# TIA_Schematic_19_Jan_2017.net
KiCad netlist of a schematic drawn in EAGLE
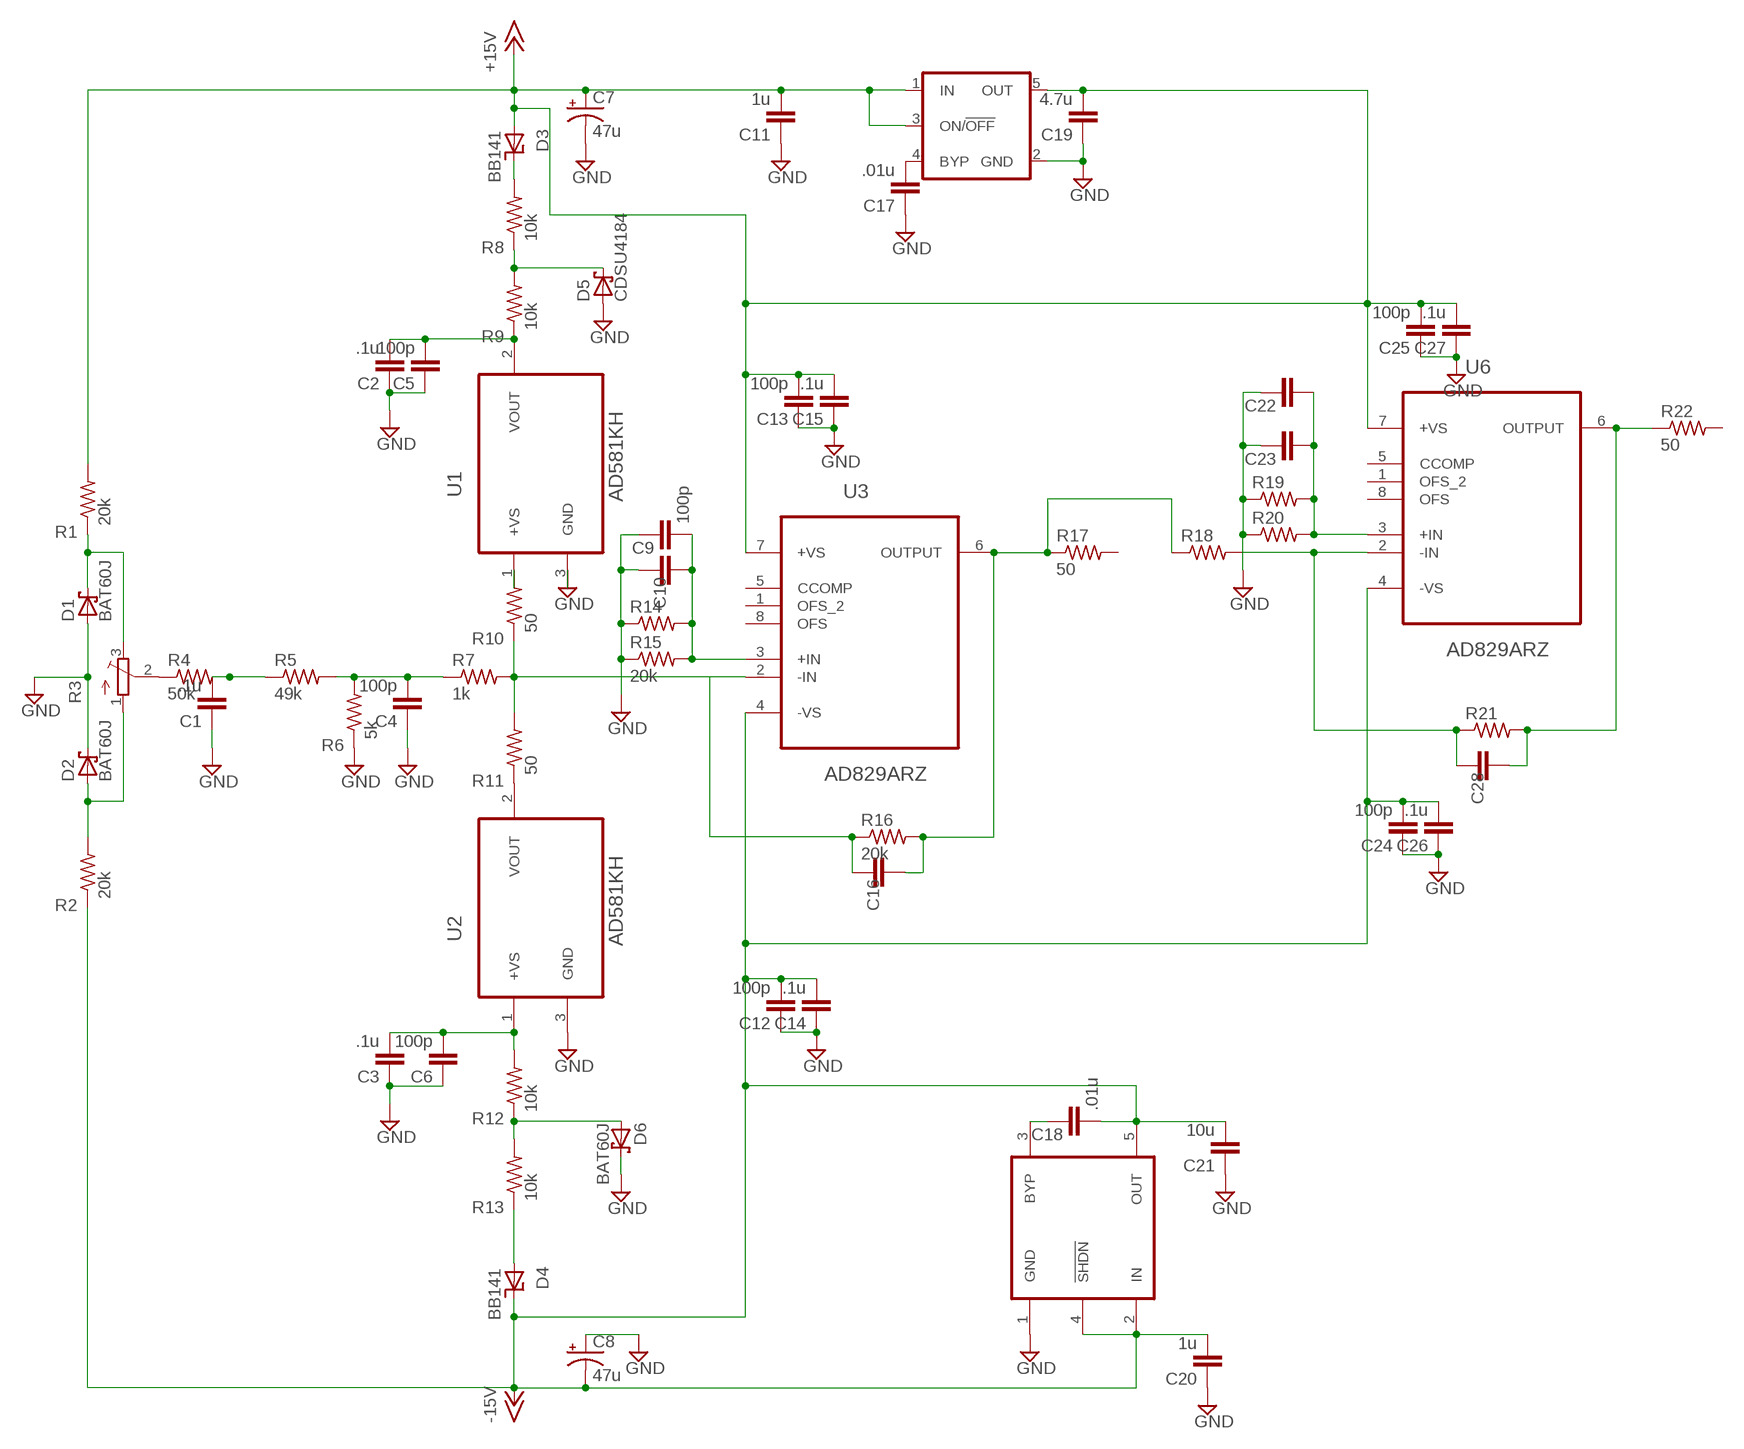
[diagram p0: schematic, sheet 1]

(export (version "E")
  (design (tool "Eeschema 10.0.6"))
  (components
    (comp (ref "C1")
      (value ".1u")
      (footprint "eagle-import:C0603")
      (libsource (lib "eagle-import") (part "C-EUC0603"))
    )
    (comp (ref "C2")
      (value ".1u")
      (footprint "eagle-import:C0603")
      (libsource (lib "eagle-import") (part "C-EUC0603"))
    )
    (comp (ref "C3")
      (value ".1u")
      (footprint "eagle-import:C0603")
      (libsource (lib "eagle-import") (part "C-EUC0603"))
    )
    (comp (ref "C4")
      (value "100p")
      (footprint "eagle-import:C0603")
      (libsource (lib "eagle-import") (part "C-EUC0603"))
    )
    (comp (ref "C5")
      (value "100p")
      (footprint "eagle-import:C0603")
      (libsource (lib "eagle-import") (part "C-EUC0603"))
    )
    (comp (ref "C6")
      (value "100p")
      (footprint "eagle-import:C0603")
      (libsource (lib "eagle-import") (part "C-EUC0603"))
    )
    (comp (ref "C7")
      (value "47u")
      (footprint "eagle-import:ETR3")
      (libsource (lib "eagle-import") (part "CPOL-USETR3"))
    )
    (comp (ref "C8")
      (value "47u")
      (footprint "eagle-import:ETR3")
      (libsource (lib "eagle-import") (part "CPOL-USETR3"))
    )
    (comp (ref "C9")
      (value "100p")
      (footprint "eagle-import:C0603")
      (libsource (lib "eagle-import") (part "C-EUC0603"))
    )
    (comp (ref "C10")
      (value "C-EUC0603")
      (footprint "eagle-import:C0603")
      (libsource (lib "eagle-import") (part "C-EUC0603"))
    )
    (comp (ref "C11")
      (value "1u")
      (footprint "eagle-import:C0603")
      (libsource (lib "eagle-import") (part "C-EUC0603"))
    )
    (comp (ref "C12")
      (value "100p")
      (footprint "eagle-import:C0603")
      (libsource (lib "eagle-import") (part "C-EUC0603"))
    )
    (comp (ref "C13")
      (value "100p")
      (footprint "eagle-import:C0603")
      (libsource (lib "eagle-import") (part "C-EUC0603"))
    )
    (comp (ref "C14")
      (value ".1u")
      (footprint "eagle-import:C0603")
      (libsource (lib "eagle-import") (part "C-EUC0603"))
    )
    (comp (ref "C15")
      (value ".1u")
      (footprint "eagle-import:C0603")
      (libsource (lib "eagle-import") (part "C-EUC0603"))
    )
    (comp (ref "C16")
      (value "C-EUC0603")
      (footprint "eagle-import:C0603")
      (libsource (lib "eagle-import") (part "C-EUC0603"))
    )
    (comp (ref "C17")
      (value ".01u")
      (footprint "eagle-import:C0603")
      (libsource (lib "eagle-import") (part "C-EUC0603"))
    )
    (comp (ref "C18")
      (value ".01u")
      (footprint "eagle-import:C0603")
      (libsource (lib "eagle-import") (part "C-EUC0603"))
    )
    (comp (ref "C19")
      (value "4.7u")
      (footprint "eagle-import:C0603")
      (libsource (lib "eagle-import") (part "C-EUC0603"))
    )
    (comp (ref "C20")
      (value "1u")
      (footprint "eagle-import:C0603")
      (libsource (lib "eagle-import") (part "C-EUC0603"))
    )
    (comp (ref "C21")
      (value "10u")
      (footprint "eagle-import:C0603")
      (libsource (lib "eagle-import") (part "C-EUC0603"))
    )
    (comp (ref "C22")
      (value "C-EUC0603")
      (footprint "eagle-import:C0603")
      (libsource (lib "eagle-import") (part "C-EUC0603"))
    )
    (comp (ref "C23")
      (value "C-EUC0603")
      (footprint "eagle-import:C0603")
      (libsource (lib "eagle-import") (part "C-EUC0603"))
    )
    (comp (ref "C24")
      (value "100p")
      (footprint "eagle-import:C0603")
      (libsource (lib "eagle-import") (part "C-EUC0603"))
    )
    (comp (ref "C25")
      (value "100p")
      (footprint "eagle-import:C0603")
      (libsource (lib "eagle-import") (part "C-EUC0603"))
    )
    (comp (ref "C26")
      (value ".1u")
      (footprint "eagle-import:C0603")
      (libsource (lib "eagle-import") (part "C-EUC0603"))
    )
    (comp (ref "C27")
      (value ".1u")
      (footprint "eagle-import:C0603")
      (libsource (lib "eagle-import") (part "C-EUC0603"))
    )
    (comp (ref "C28")
      (value "C-EUC0603")
      (footprint "eagle-import:C0603")
      (libsource (lib "eagle-import") (part "C-EUC0603"))
    )
    (comp (ref "D1")
      (value "BAT60J")
      (footprint "eagle-import:SOD323_ST")
      (libsource (lib "eagle-import") (part "BAT60J"))
    )
    (comp (ref "D2")
      (value "BAT60J")
      (footprint "eagle-import:SOD323_ST")
      (libsource (lib "eagle-import") (part "BAT60J"))
    )
    (comp (ref "D3")
      (value "BB141")
      (footprint "eagle-import:SOD523")
      (libsource (lib "eagle-import") (part "BB141"))
    )
    (comp (ref "D4")
      (value "BB141")
      (footprint "eagle-import:SOD523")
      (libsource (lib "eagle-import") (part "BB141"))
    )
    (comp (ref "D5")
      (value "CDSU4184")
      (footprint "eagle-import:SOD323_ST")
      (libsource (lib "eagle-import") (part "BAT60J"))
    )
    (comp (ref "D6")
      (value "BAT60J")
      (footprint "eagle-import:SOD323_ST")
      (libsource (lib "eagle-import") (part "BAT60J"))
    )
    (comp (ref "R1")
      (value "20k")
      (footprint "eagle-import:R0603")
      (libsource (lib "eagle-import") (part "R-US_R0603"))
    )
    (comp (ref "R2")
      (value "20k")
      (footprint "eagle-import:R0603")
      (libsource (lib "eagle-import") (part "R-US_R0603"))
    )
    (comp (ref "R3")
      (value "TRIM_EU-3223G")
      (footprint "eagle-import:3223G")
      (libsource (lib "eagle-import") (part "TRIM_EU-3223G"))
    )
    (comp (ref "R4")
      (value "50k")
      (footprint "eagle-import:R0603")
      (libsource (lib "eagle-import") (part "R-US_R0603"))
    )
    (comp (ref "R5")
      (value "49k")
      (footprint "eagle-import:R0603")
      (libsource (lib "eagle-import") (part "R-US_R0603"))
    )
    (comp (ref "R6")
      (value "5k")
      (footprint "eagle-import:R0603")
      (libsource (lib "eagle-import") (part "R-US_R0603"))
    )
    (comp (ref "R7")
      (value "1k")
      (footprint "eagle-import:R0603")
      (libsource (lib "eagle-import") (part "R-US_R0603"))
    )
    (comp (ref "R8")
      (value "10k")
      (footprint "eagle-import:R0603")
      (libsource (lib "eagle-import") (part "R-US_R0603"))
    )
    (comp (ref "R9")
      (value "10k")
      (footprint "eagle-import:R0603")
      (libsource (lib "eagle-import") (part "R-US_R0603"))
    )
    (comp (ref "R10")
      (value "50")
      (footprint "eagle-import:R0603")
      (libsource (lib "eagle-import") (part "R-US_R0603"))
    )
    (comp (ref "R11")
      (value "50")
      (footprint "eagle-import:R0603")
      (libsource (lib "eagle-import") (part "R-US_R0603"))
    )
    (comp (ref "R12")
      (value "10k")
      (footprint "eagle-import:R0603")
      (libsource (lib "eagle-import") (part "R-US_R0603"))
    )
    (comp (ref "R13")
      (value "10k")
      (footprint "eagle-import:R0603")
      (libsource (lib "eagle-import") (part "R-US_R0603"))
    )
    (comp (ref "R14")
      (value "R-US_R0603")
      (footprint "eagle-import:R0603")
      (libsource (lib "eagle-import") (part "R-US_R0603"))
    )
    (comp (ref "R15")
      (value "20k")
      (footprint "eagle-import:R0603")
      (libsource (lib "eagle-import") (part "R-US_R0603"))
    )
    (comp (ref "R16")
      (value "20k")
      (footprint "eagle-import:R0603")
      (libsource (lib "eagle-import") (part "R-US_R0603"))
    )
    (comp (ref "R17")
      (value "50")
      (footprint "eagle-import:R0603")
      (libsource (lib "eagle-import") (part "R-US_R0603"))
    )
    (comp (ref "R18")
      (value "R-US_R0603")
      (footprint "eagle-import:R0603")
      (libsource (lib "eagle-import") (part "R-US_R0603"))
    )
    (comp (ref "R19")
      (value "R-US_R0603")
      (footprint "eagle-import:R0603")
      (libsource (lib "eagle-import") (part "R-US_R0603"))
    )
    (comp (ref "R20")
      (value "R-US_R0603")
      (footprint "eagle-import:R0603")
      (libsource (lib "eagle-import") (part "R-US_R0603"))
    )
    (comp (ref "R21")
      (value "R-US_R0603")
      (footprint "eagle-import:R0603")
      (libsource (lib "eagle-import") (part "R-US_R0603"))
    )
    (comp (ref "R22")
      (value "50")
      (footprint "eagle-import:R0603")
      (libsource (lib "eagle-import") (part "R-US_R0603"))
    )
    (comp (ref "U1")
      (value "AD581KH")
      (footprint "eagle-import:TO254P939X470-3P")
      (libsource (lib "eagle-import") (part "AD581KH"))
    )
    (comp (ref "U2")
      (value "AD581KH")
      (footprint "eagle-import:TO254P939X470-3P")
      (libsource (lib "eagle-import") (part "AD581KH"))
    )
    (comp (ref "U3")
      (value "AD829ARZ")
      (footprint "eagle-import:SOIC127P600X175-8N")
      (libsource (lib "eagle-import") (part "AD829ARZ"))
    )
    (comp (ref "U4")
      (value "LP2992M5")
      (footprint "eagle-import:SOT23-5")
      (libsource (lib "eagle-import") (part "LP2992M5"))
    )
    (comp (ref "U5")
      (value "LT1964")
      (footprint "eagle-import:SOT23-5")
      (libsource (lib "eagle-import") (part "LT1964"))
    )
    (comp (ref "U6")
      (value "AD829ARZ")
      (footprint "eagle-import:SOIC127P600X175-8N")
      (libsource (lib "eagle-import") (part "AD829ARZ"))
    )
  )
  (nets
    (net (code "1") (name "+15V") (class "Default")
      (node (ref "C11") (pin "2") (pinfunction "2_2") (pintype "passive"))
      (node (ref "C13") (pin "2") (pinfunction "2_2") (pintype "passive"))
      (node (ref "C15") (pin "2") (pinfunction "2_2") (pintype "passive"))
      (node (ref "C19") (pin "2") (pinfunction "2_2") (pintype "passive"))
      (node (ref "C25") (pin "2") (pinfunction "2_2") (pintype "passive"))
      (node (ref "C27") (pin "2") (pinfunction "2_2") (pintype "passive"))
      (node (ref "C7") (pin "+") (pinfunction "+_+") (pintype "passive"))
      (node (ref "D3") (pin "A") (pinfunction "A_A") (pintype "passive"))
      (node (ref "R1") (pin "2") (pinfunction "2_2") (pintype "passive"))
      (node (ref "U3") (pin "7") (pinfunction "+VS_7") (pintype "power_in"))
      (node (ref "U4") (pin "1") (pinfunction "IN_1") (pintype "input"))
      (node (ref "U4") (pin "3") (pinfunction "ON/~{OFF}_3") (pintype "input"))
      (node (ref "U4") (pin "5") (pinfunction "OUT_5") (pintype "passive"))
      (node (ref "U6") (pin "7") (pinfunction "+VS_7") (pintype "power_in"))
    )
    (net (code "2") (name "-15V") (class "Default")
      (node (ref "C12") (pin "2") (pinfunction "2_2") (pintype "passive"))
      (node (ref "C14") (pin "2") (pinfunction "2_2") (pintype "passive"))
      (node (ref "C18") (pin "2") (pinfunction "2_2") (pintype "passive"))
      (node (ref "C20") (pin "2") (pinfunction "2_2") (pintype "passive"))
      (node (ref "C21") (pin "2") (pinfunction "2_2") (pintype "passive"))
      (node (ref "C24") (pin "2") (pinfunction "2_2") (pintype "passive"))
      (node (ref "C26") (pin "2") (pinfunction "2_2") (pintype "passive"))
      (node (ref "C8") (pin "-") (pinfunction "-_-") (pintype "passive"))
      (node (ref "D4") (pin "C") (pinfunction "C_C") (pintype "passive"))
      (node (ref "R2") (pin "1") (pinfunction "1_1") (pintype "passive"))
      (node (ref "U3") (pin "4") (pinfunction "-VS_4") (pintype "power_in"))
      (node (ref "U5") (pin "2") (pinfunction "IN_2") (pintype "bidirectional"))
      (node (ref "U5") (pin "4") (pinfunction "~{SHDN}_4") (pintype "bidirectional"))
      (node (ref "U5") (pin "5") (pinfunction "OUT_5") (pintype "bidirectional"))
      (node (ref "U6") (pin "4") (pinfunction "-VS_4") (pintype "power_in"))
    )
    (net (code "3") (name "GND") (class "Default")
      (node (ref "C1") (pin "1") (pinfunction "1_1") (pintype "passive"))
      (node (ref "C10") (pin "1") (pinfunction "1_1") (pintype "passive"))
      (node (ref "C11") (pin "1") (pinfunction "1_1") (pintype "passive"))
      (node (ref "C12") (pin "1") (pinfunction "1_1") (pintype "passive"))
      (node (ref "C13") (pin "1") (pinfunction "1_1") (pintype "passive"))
      (node (ref "C14") (pin "1") (pinfunction "1_1") (pintype "passive"))
      (node (ref "C15") (pin "1") (pinfunction "1_1") (pintype "passive"))
      (node (ref "C17") (pin "1") (pinfunction "1_1") (pintype "passive"))
      (node (ref "C19") (pin "1") (pinfunction "1_1") (pintype "passive"))
      (node (ref "C2") (pin "1") (pinfunction "1_1") (pintype "passive"))
      (node (ref "C20") (pin "1") (pinfunction "1_1") (pintype "passive"))
      (node (ref "C21") (pin "1") (pinfunction "1_1") (pintype "passive"))
      (node (ref "C22") (pin "1") (pinfunction "1_1") (pintype "passive"))
      (node (ref "C23") (pin "1") (pinfunction "1_1") (pintype "passive"))
      (node (ref "C24") (pin "1") (pinfunction "1_1") (pintype "passive"))
      (node (ref "C25") (pin "1") (pinfunction "1_1") (pintype "passive"))
      (node (ref "C26") (pin "1") (pinfunction "1_1") (pintype "passive"))
      (node (ref "C27") (pin "1") (pinfunction "1_1") (pintype "passive"))
      (node (ref "C3") (pin "1") (pinfunction "1_1") (pintype "passive"))
      (node (ref "C4") (pin "1") (pinfunction "1_1") (pintype "passive"))
      (node (ref "C5") (pin "1") (pinfunction "1_1") (pintype "passive"))
      (node (ref "C6") (pin "1") (pinfunction "1_1") (pintype "passive"))
      (node (ref "C7") (pin "-") (pinfunction "-_-") (pintype "passive"))
      (node (ref "C8") (pin "+") (pinfunction "+_+") (pintype "passive"))
      (node (ref "C9") (pin "1") (pinfunction "1_1") (pintype "passive"))
      (node (ref "D1") (pin "A") (pinfunction "A_A") (pintype "passive"))
      (node (ref "D2") (pin "C") (pinfunction "C_C") (pintype "passive"))
      (node (ref "D5") (pin "A") (pinfunction "A_A") (pintype "passive"))
      (node (ref "D6") (pin "C") (pinfunction "C_C") (pintype "passive"))
      (node (ref "R14") (pin "1") (pinfunction "1_1") (pintype "passive"))
      (node (ref "R15") (pin "1") (pinfunction "1_1") (pintype "passive"))
      (node (ref "R19") (pin "1") (pinfunction "1_1") (pintype "passive"))
      (node (ref "R20") (pin "1") (pinfunction "1_1") (pintype "passive"))
      (node (ref "R6") (pin "1") (pinfunction "1_1") (pintype "passive"))
      (node (ref "U1") (pin "3") (pinfunction "GND_3") (pintype "passive"))
      (node (ref "U2") (pin "3") (pinfunction "GND_3") (pintype "passive"))
      (node (ref "U4") (pin "2") (pinfunction "GND_2") (pintype "power_in"))
      (node (ref "U5") (pin "1") (pinfunction "GND_1") (pintype "bidirectional"))
    )
    (net (code "4") (name "Net-(C1-Pad2)") (class "Default")
      (node (ref "C1") (pin "2") (pinfunction "2_2") (pintype "passive"))
      (node (ref "R4") (pin "2") (pinfunction "2_2") (pintype "passive"))
      (node (ref "R5") (pin "1") (pinfunction "1_1") (pintype "passive"))
    )
    (net (code "5") (name "Net-(C4-Pad2)") (class "Default")
      (node (ref "C4") (pin "2") (pinfunction "2_2") (pintype "passive"))
      (node (ref "R5") (pin "2") (pinfunction "2_2") (pintype "passive"))
      (node (ref "R6") (pin "2") (pinfunction "2_2") (pintype "passive"))
      (node (ref "R7") (pin "1") (pinfunction "1_1") (pintype "passive"))
    )
    (net (code "6") (name "Net-(D3-PadC)") (class "Default")
      (node (ref "D3") (pin "C") (pinfunction "C_C") (pintype "passive"))
      (node (ref "R8") (pin "2") (pinfunction "2_2") (pintype "passive"))
    )
    (net (code "7") (name "Net-(D4-PadA)") (class "Default")
      (node (ref "D4") (pin "A") (pinfunction "A_A") (pintype "passive"))
      (node (ref "R13") (pin "1") (pinfunction "1_1") (pintype "passive"))
    )
    (net (code "8") (name "Net-(D5-PadC)") (class "Default")
      (node (ref "D5") (pin "C") (pinfunction "C_C") (pintype "passive"))
      (node (ref "R8") (pin "1") (pinfunction "1_1") (pintype "passive"))
      (node (ref "R9") (pin "2") (pinfunction "2_2") (pintype "passive"))
    )
    (net (code "9") (name "Net-(D6-PadA)") (class "Default")
      (node (ref "D6") (pin "A") (pinfunction "A_A") (pintype "passive"))
      (node (ref "R12") (pin "1") (pinfunction "1_1") (pintype "passive"))
      (node (ref "R13") (pin "2") (pinfunction "2_2") (pintype "passive"))
    )
    (net (code "10") (name "Net-(R3-A)") (class "Default")
      (node (ref "D2") (pin "A") (pinfunction "A_A") (pintype "passive"))
      (node (ref "R2") (pin "2") (pinfunction "2_2") (pintype "passive"))
      (node (ref "R3") (pin "1") (pinfunction "A_1") (pintype "passive"))
    )
    (net (code "11") (name "Net-(R3-E)") (class "Default")
      (node (ref "D1") (pin "C") (pinfunction "C_C") (pintype "passive"))
      (node (ref "R1") (pin "1") (pinfunction "1_1") (pintype "passive"))
      (node (ref "R3") (pin "3") (pinfunction "E_3") (pintype "passive"))
    )
    (net (code "12") (name "Net-(R3-S)") (class "Default")
      (node (ref "R3") (pin "2") (pinfunction "S_2") (pintype "passive"))
      (node (ref "R4") (pin "1") (pinfunction "1_1") (pintype "passive"))
    )
    (net (code "13") (name "Net-(U1-+VS)") (class "Default")
      (node (ref "R10") (pin "2") (pinfunction "2_2") (pintype "passive"))
      (node (ref "U1") (pin "1") (pinfunction "+VS_1") (pintype "power_in"))
    )
    (net (code "14") (name "Net-(U1-VOUT)") (class "Default")
      (node (ref "C2") (pin "2") (pinfunction "2_2") (pintype "passive"))
      (node (ref "C5") (pin "2") (pinfunction "2_2") (pintype "passive"))
      (node (ref "R9") (pin "1") (pinfunction "1_1") (pintype "passive"))
      (node (ref "U1") (pin "2") (pinfunction "VOUT_2") (pintype "output"))
    )
    (net (code "15") (name "Net-(U2-+VS)") (class "Default")
      (node (ref "C3") (pin "2") (pinfunction "2_2") (pintype "passive"))
      (node (ref "C6") (pin "2") (pinfunction "2_2") (pintype "passive"))
      (node (ref "R12") (pin "2") (pinfunction "2_2") (pintype "passive"))
      (node (ref "U2") (pin "1") (pinfunction "+VS_1") (pintype "power_in"))
    )
    (net (code "16") (name "Net-(U2-VOUT)") (class "Default")
      (node (ref "R11") (pin "1") (pinfunction "1_1") (pintype "passive"))
      (node (ref "U2") (pin "2") (pinfunction "VOUT_2") (pintype "output"))
    )
    (net (code "17") (name "Net-(U3-+IN)") (class "Default")
      (node (ref "C10") (pin "2") (pinfunction "2_2") (pintype "passive"))
      (node (ref "C9") (pin "2") (pinfunction "2_2") (pintype "passive"))
      (node (ref "R14") (pin "2") (pinfunction "2_2") (pintype "passive"))
      (node (ref "R15") (pin "2") (pinfunction "2_2") (pintype "passive"))
      (node (ref "U3") (pin "3") (pinfunction "+IN_3") (pintype "input"))
    )
    (net (code "18") (name "Net-(U3--IN)") (class "Default")
      (node (ref "C16") (pin "1") (pinfunction "1_1") (pintype "passive"))
      (node (ref "R10") (pin "1") (pinfunction "1_1") (pintype "passive"))
      (node (ref "R11") (pin "2") (pinfunction "2_2") (pintype "passive"))
      (node (ref "R16") (pin "1") (pinfunction "1_1") (pintype "passive"))
      (node (ref "R7") (pin "2") (pinfunction "2_2") (pintype "passive"))
      (node (ref "U3") (pin "2") (pinfunction "-IN_2") (pintype "input"))
    )
    (net (code "19") (name "Net-(U3-OUTPUT)") (class "Default")
      (node (ref "C16") (pin "2") (pinfunction "2_2") (pintype "passive"))
      (node (ref "R16") (pin "2") (pinfunction "2_2") (pintype "passive"))
      (node (ref "R17") (pin "1") (pinfunction "1_1") (pintype "passive"))
      (node (ref "R18") (pin "1") (pinfunction "1_1") (pintype "passive"))
      (node (ref "U3") (pin "6") (pinfunction "OUTPUT_6") (pintype "output"))
    )
    (net (code "20") (name "Net-(U4-BYP)") (class "Default")
      (node (ref "C17") (pin "2") (pinfunction "2_2") (pintype "passive"))
      (node (ref "U4") (pin "4") (pinfunction "BYP_4") (pintype "passive"))
    )
    (net (code "21") (name "Net-(U5-BYP)") (class "Default")
      (node (ref "C18") (pin "1") (pinfunction "1_1") (pintype "passive"))
      (node (ref "U5") (pin "3") (pinfunction "BYP_3") (pintype "bidirectional"))
    )
    (net (code "22") (name "Net-(U6-+IN)") (class "Default")
      (node (ref "C22") (pin "2") (pinfunction "2_2") (pintype "passive"))
      (node (ref "C23") (pin "2") (pinfunction "2_2") (pintype "passive"))
      (node (ref "R19") (pin "2") (pinfunction "2_2") (pintype "passive"))
      (node (ref "R20") (pin "2") (pinfunction "2_2") (pintype "passive"))
      (node (ref "U6") (pin "3") (pinfunction "+IN_3") (pintype "input"))
    )
    (net (code "23") (name "Net-(U6--IN)") (class "Default")
      (node (ref "C28") (pin "1") (pinfunction "1_1") (pintype "passive"))
      (node (ref "R18") (pin "2") (pinfunction "2_2") (pintype "passive"))
      (node (ref "R21") (pin "1") (pinfunction "1_1") (pintype "passive"))
      (node (ref "U6") (pin "2") (pinfunction "-IN_2") (pintype "input"))
    )
    (net (code "24") (name "Net-(U6-OUTPUT)") (class "Default")
      (node (ref "C28") (pin "2") (pinfunction "2_2") (pintype "passive"))
      (node (ref "R21") (pin "2") (pinfunction "2_2") (pintype "passive"))
      (node (ref "R22") (pin "1") (pinfunction "1_1") (pintype "passive"))
      (node (ref "U6") (pin "6") (pinfunction "OUTPUT_6") (pintype "output"))
    )
    (net (code "25") (name "unconnected-(R17-Pad2)") (class "Default")
      (node (ref "R17") (pin "2") (pinfunction "2_2") (pintype "passive"))
    )
    (net (code "26") (name "unconnected-(R22-Pad2)") (class "Default")
      (node (ref "R22") (pin "2") (pinfunction "2_2") (pintype "passive"))
    )
    (net (code "27") (name "unconnected-(U3-CCOMP-Pad5)") (class "Default")
      (node (ref "U3") (pin "5") (pinfunction "CCOMP_5") (pintype "passive"))
    )
    (net (code "28") (name "unconnected-(U3-OFS-Pad8)") (class "Default")
      (node (ref "U3") (pin "8") (pinfunction "OFS_8") (pintype "passive"))
    )
    (net (code "29") (name "unconnected-(U3-OFS_2-Pad1)") (class "Default")
      (node (ref "U3") (pin "1") (pinfunction "OFS_2_1") (pintype "passive"))
    )
    (net (code "30") (name "unconnected-(U6-CCOMP-Pad5)") (class "Default")
      (node (ref "U6") (pin "5") (pinfunction "CCOMP_5") (pintype "passive"))
    )
    (net (code "31") (name "unconnected-(U6-OFS-Pad8)") (class "Default")
      (node (ref "U6") (pin "8") (pinfunction "OFS_8") (pintype "passive"))
    )
    (net (code "32") (name "unconnected-(U6-OFS_2-Pad1)") (class "Default")
      (node (ref "U6") (pin "1") (pinfunction "OFS_2_1") (pintype "passive"))
    )
  )
)
